# sbcp-master.net
KiCad netlist of a schematic drawn in Altium Designer
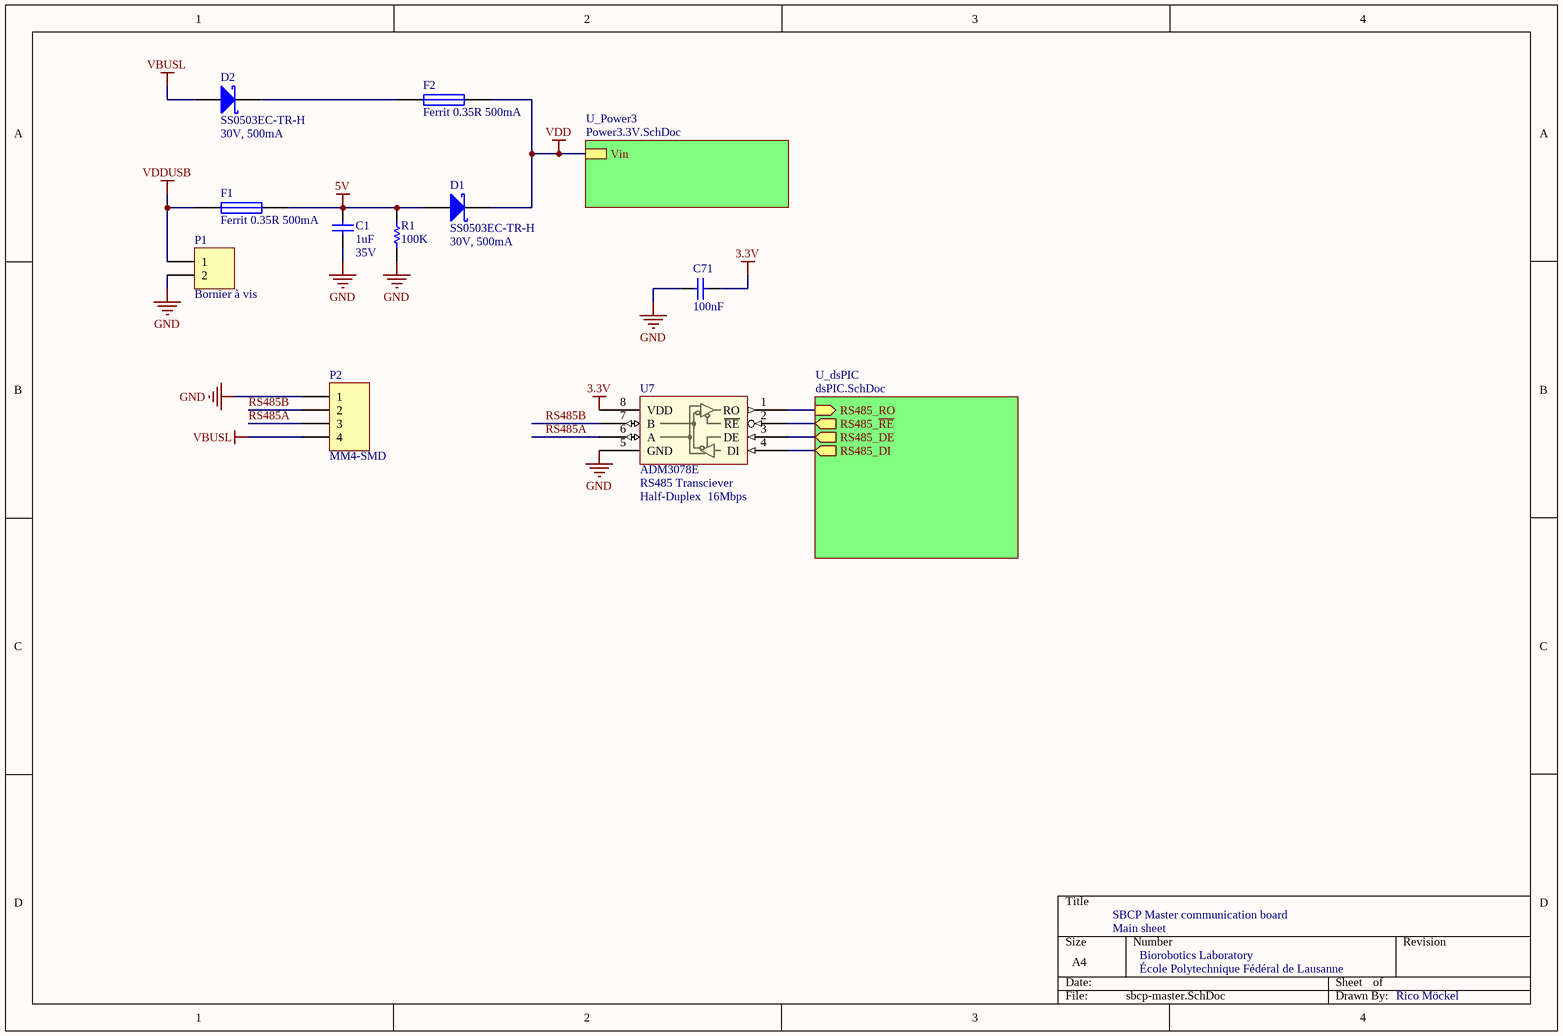
[diagram p0: sbcp-master.SchDoc]

(export (version "E")
  (design (tool "Eeschema 10.0.6"))
  (components
    (comp (ref "C1")
      (value "1uF")
      (footprint "CAPC1608N")
      (description "Capacitor")
      (fields
        (field (name "VOLTAGE") "35V")
        (field (name "Comment") "1uF, 35V")
        (field (name "PUBLISHER") "Altium Limited")
      )
      (libsource (lib "Miscellaneous Devices") (part "Cap"))
    )
    (comp (ref "C71")
      (value "100nF")
      (footprint "CAPC1005N")
      (description "Capacitor")
      (fields (field (name "PUBLISHER") "Altium Limited"))
      (libsource (lib "Miscellaneous Devices") (part "Cap"))
    )
    (comp (ref "D1")
      (value "SS0503EC-TR-H")
      (footprint "RESC1005N")
      (description "Schottky Diode")
      (fields (field (name "VALUES") "30V, 500mA") (field (name "PUBLISHER") "Altium Limited"))
      (libsource (lib "Miscellaneous Devices") (part "D Schottky"))
    )
    (comp (ref "D2")
      (value "SS0503EC-TR-H")
      (footprint "RESC1005N")
      (description "Schottky Diode")
      (fields (field (name "VALUES") "30V, 500mA") (field (name "PUBLISHER") "Altium Limited"))
      (libsource (lib "Miscellaneous Devices") (part "D Schottky"))
    )
    (comp (ref "F1")
      (value "Ferrit 0.35R 500mA")
      (footprint "RESC1608N_R")
      (description "Ferrit Bead")
      (fields (field (name "PUBLISHER") "Altium Limited"))
      (libsource (lib "Miscellaneous Devices") (part "Fuse 1"))
    )
    (comp (ref "F2")
      (value "Ferrit 0.35R 500mA")
      (footprint "RESC1608N_R")
      (description "Ferrit Bead")
      (fields (field (name "PUBLISHER") "Altium Limited"))
      (libsource (lib "Miscellaneous Devices") (part "Fuse 1"))
    )
    (comp (ref "P1")
      (value "Bornier à vis")
      (description "Header, 2-Pin")
      (fields (field (name "PUBLISHER") "Altium Limited"))
      (libsource (lib "Miscellaneous Connectors") (part "Header 2"))
    )
    (comp (ref "P2")
      (value "MM4-SMD")
      (footprint "MM4-SMD")
      (description "Header, 4-Pin")
      (fields (field (name "PUBLISHER") "Altium Limited"))
      (libsource (lib "Miscellaneous Connectors") (part "Header 4"))
    )
    (comp (ref "R1")
      (value "100K")
      (footprint "RESC1005N")
      (description "Resistor")
      (fields (field (name "PUBLISHER") "Altium Limited"))
      (libsource (lib "Miscellaneous Devices") (part "Res1"))
    )
    (comp (ref "U7")
      (value "ADM3078E")
      (footprint "SOIC-8_M")
      (description "Half-Duplex RS485 Transciever, 3.3V, 16Mbps")
      (libsource (lib "Roombots") (part "ADM3078E"))
    )
  )
  (nets
    (net (code "1") (name "/RS485A") (class "Default")
      (node (ref "P2") (pin "3") (pinfunction "3_3") (pintype "passive"))
      (node (ref "U7") (pin "6") (pinfunction "A_6") (pintype "bidirectional"))
    )
    (net (code "2") (name "/RS485B") (class "Default")
      (node (ref "P2") (pin "2") (pinfunction "2_2") (pintype "passive"))
      (node (ref "U7") (pin "7") (pinfunction "B_7") (pintype "bidirectional"))
    )
    (net (code "3") (name "/RS485_DE") (class "Default")
      (node (ref "U7") (pin "3") (pinfunction "DE_3") (pintype "input"))
    )
    (net (code "4") (name "/RS485_DI") (class "Default")
      (node (ref "U7") (pin "4") (pinfunction "DI_4") (pintype "input"))
    )
    (net (code "5") (name "/RS485_RO") (class "Default")
      (node (ref "U7") (pin "1") (pinfunction "RO_1") (pintype "output"))
    )
    (net (code "6") (name "/RS485_~{RE}") (class "Default")
      (node (ref "U7") (pin "2") (pinfunction "~{RE}_2") (pintype "input"))
    )
    (net (code "7") (name "3.3V") (class "Default")
      (node (ref "C71") (pin "1") (pinfunction "1_1") (pintype "passive"))
      (node (ref "U7") (pin "8") (pinfunction "VDD_8") (pintype "power_in"))
    )
    (net (code "8") (name "5V") (class "Default")
      (node (ref "C1") (pin "2") (pinfunction "2_2") (pintype "passive"))
      (node (ref "D1") (pin "1") (pinfunction "A_1") (pintype "passive"))
      (node (ref "F1") (pin "2") (pinfunction "2_2") (pintype "passive"))
      (node (ref "R1") (pin "1") (pinfunction "1_1") (pintype "passive"))
    )
    (net (code "9") (name "GND") (class "Default")
      (node (ref "C1") (pin "1") (pinfunction "1_1") (pintype "passive"))
      (node (ref "C71") (pin "2") (pinfunction "2_2") (pintype "passive"))
      (node (ref "P1") (pin "2") (pinfunction "2_2") (pintype "passive"))
      (node (ref "P2") (pin "1") (pinfunction "1_1") (pintype "passive"))
      (node (ref "R1") (pin "2") (pinfunction "2_2") (pintype "passive"))
      (node (ref "U7") (pin "5") (pinfunction "GND_5") (pintype "power_in"))
    )
    (net (code "10") (name "Net-(D2-K)") (class "Default")
      (node (ref "D2") (pin "2") (pinfunction "K_2") (pintype "passive"))
      (node (ref "F2") (pin "1") (pinfunction "1_1") (pintype "passive"))
    )
    (net (code "11") (name "VBUSL") (class "Default")
      (node (ref "D2") (pin "1") (pinfunction "A_1") (pintype "passive"))
      (node (ref "P2") (pin "4") (pinfunction "4_4") (pintype "passive"))
    )
    (net (code "12") (name "VDD") (class "Default")
      (node (ref "D1") (pin "2") (pinfunction "K_2") (pintype "passive"))
      (node (ref "F2") (pin "2") (pinfunction "2_2") (pintype "passive"))
    )
    (net (code "13") (name "VDDUSB") (class "Default")
      (node (ref "F1") (pin "1") (pinfunction "1_1") (pintype "passive"))
      (node (ref "P1") (pin "1") (pinfunction "1_1") (pintype "passive"))
    )
  )
)
